# RCM-PBB_E1.net
KiCad netlist of a schematic drawn in EAGLE
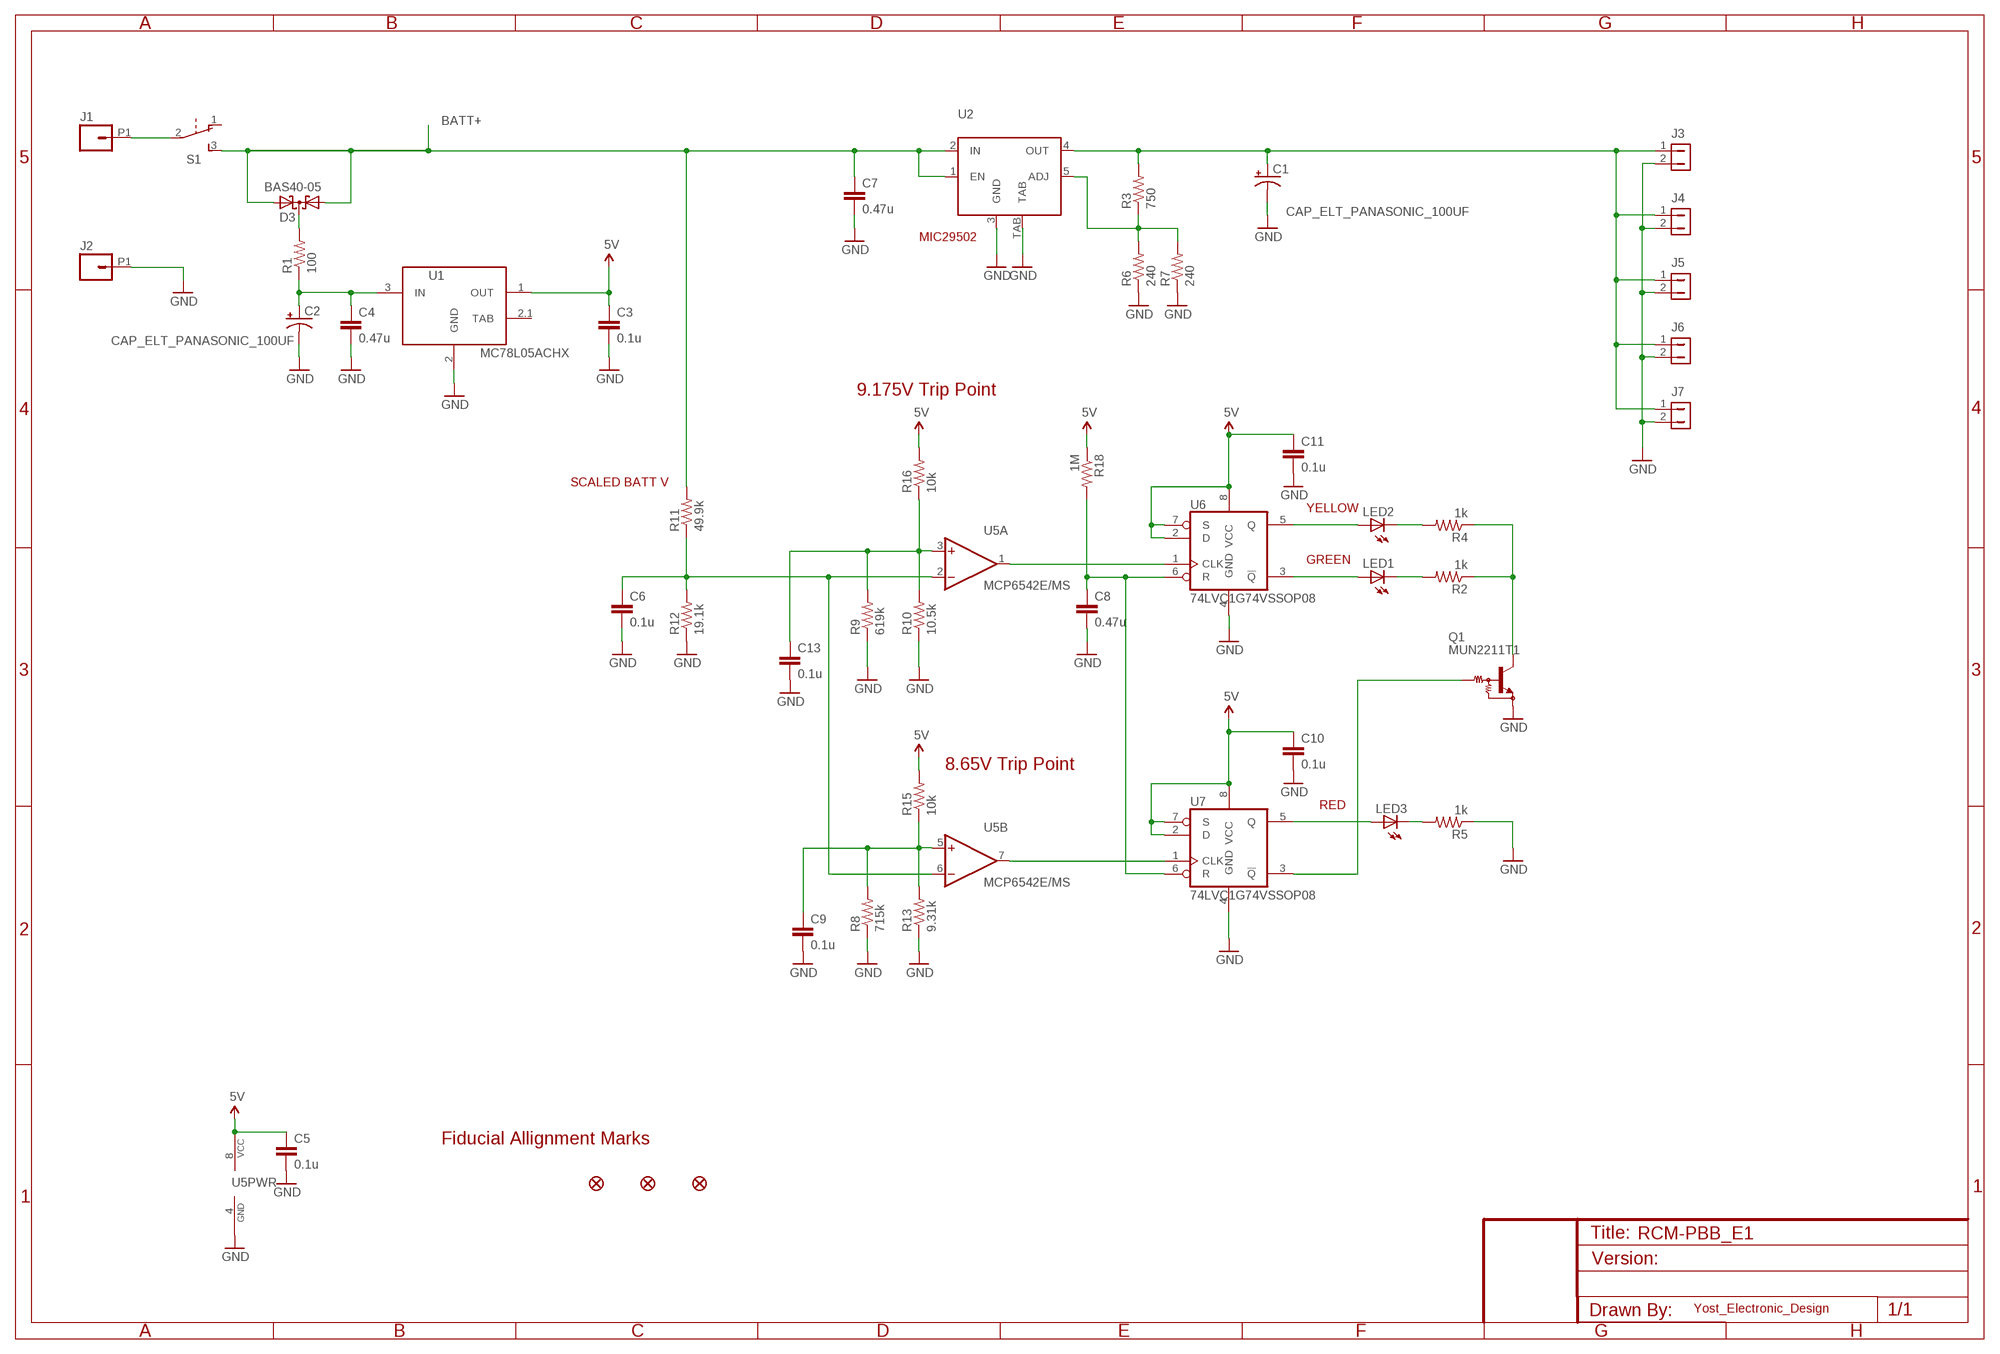
[diagram p0: schematic, sheet 1]

(export (version "E")
  (design (tool "Eeschema 10.0.6"))
  (components
    (comp (ref "C1")
      (value "CAP_ELT_PANASONIC_100UF")
      (footprint "eagle-import:PANASONIC-D8-ELT-CAP")
      (libsource (lib "eagle-import") (part "CAP_ELT_PANASONIC_100UF"))
    )
    (comp (ref "C2")
      (value "CAP_ELT_PANASONIC_100UF")
      (footprint "eagle-import:PANASONIC-D8-ELT-CAP")
      (libsource (lib "eagle-import") (part "CAP_ELT_PANASONIC_100UF"))
    )
    (comp (ref "C3")
      (value "0.1u")
      (footprint "eagle-import:0805")
      (libsource (lib "eagle-import") (part "CAP0805"))
    )
    (comp (ref "C4")
      (value "0.47u")
      (footprint "eagle-import:0805")
      (libsource (lib "eagle-import") (part "CAP0805"))
    )
    (comp (ref "C5")
      (value "0.1u")
      (footprint "eagle-import:0805")
      (libsource (lib "eagle-import") (part "CAP0805"))
    )
    (comp (ref "C6")
      (value "0.1u")
      (footprint "eagle-import:0805")
      (libsource (lib "eagle-import") (part "CAP0805"))
    )
    (comp (ref "C7")
      (value "0.47u")
      (footprint "eagle-import:0805")
      (libsource (lib "eagle-import") (part "CAP0805"))
    )
    (comp (ref "C8")
      (value "0.47u")
      (footprint "eagle-import:0805")
      (libsource (lib "eagle-import") (part "CAP0805"))
    )
    (comp (ref "C9")
      (value "0.1u")
      (footprint "eagle-import:0805")
      (libsource (lib "eagle-import") (part "CAP0805"))
    )
    (comp (ref "C10")
      (value "0.1u")
      (footprint "eagle-import:0805")
      (libsource (lib "eagle-import") (part "CAP0805"))
    )
    (comp (ref "C11")
      (value "0.1u")
      (footprint "eagle-import:0805")
      (libsource (lib "eagle-import") (part "CAP0805"))
    )
    (comp (ref "C13")
      (value "0.1u")
      (footprint "eagle-import:0805")
      (libsource (lib "eagle-import") (part "CAP0805"))
    )
    (comp (ref "D3")
      (value "BAS40-05")
      (footprint "eagle-import:SOT23")
      (libsource (lib "eagle-import") (part "BAS40-05"))
    )
    (comp (ref "J1")
      (value "ANDERSON_POWER_POLE")
      (footprint "eagle-import:ANDERSON_POWER_POLE")
      (libsource (lib "eagle-import") (part "ANDERSON_POWER_POLE"))
    )
    (comp (ref "J2")
      (value "ANDERSON_POWER_POLE")
      (footprint "eagle-import:ANDERSON_POWER_POLE")
      (libsource (lib "eagle-import") (part "ANDERSON_POWER_POLE"))
    )
    (comp (ref "J3")
      (value "CON1X2_SHROUDED")
      (footprint "eagle-import:HEADER_1X2_SHROUDED")
      (libsource (lib "eagle-import") (part "CON1X2_SHROUDED"))
    )
    (comp (ref "J4")
      (value "CON1X2_SHROUDED")
      (footprint "eagle-import:HEADER_1X2_SHROUDED")
      (libsource (lib "eagle-import") (part "CON1X2_SHROUDED"))
    )
    (comp (ref "J5")
      (value "CON1X2_SHROUDED")
      (footprint "eagle-import:HEADER_1X2_SHROUDED")
      (libsource (lib "eagle-import") (part "CON1X2_SHROUDED"))
    )
    (comp (ref "J6")
      (value "CON1X2_SHROUDED")
      (footprint "eagle-import:HEADER_1X2_SHROUDED")
      (libsource (lib "eagle-import") (part "CON1X2_SHROUDED"))
    )
    (comp (ref "J7")
      (value "CON1X2_SHROUDED")
      (footprint "eagle-import:HEADER_1X2_SHROUDED")
      (libsource (lib "eagle-import") (part "CON1X2_SHROUDED"))
    )
    (comp (ref "JP4")
      (value "FIDUCIAL1X2.5")
      (footprint "eagle-import:FIDUCIAL-1X2.5")
      (libsource (lib "eagle-import") (part "FIDUCIAL1X2.5"))
    )
    (comp (ref "JP5")
      (value "FIDUCIAL1X2.5")
      (footprint "eagle-import:FIDUCIAL-1X2.5")
      (libsource (lib "eagle-import") (part "FIDUCIAL1X2.5"))
    )
    (comp (ref "JP6")
      (value "FIDUCIAL1X2.5")
      (footprint "eagle-import:FIDUCIAL-1X2.5")
      (libsource (lib "eagle-import") (part "FIDUCIAL1X2.5"))
    )
    (comp (ref "LED1")
      (value "LEDCHIPLED_0805")
      (footprint "eagle-import:CHIPLED_0805")
      (libsource (lib "eagle-import") (part "LEDCHIPLED_0805"))
    )
    (comp (ref "LED2")
      (value "LEDCHIPLED_0805")
      (footprint "eagle-import:CHIPLED_0805")
      (libsource (lib "eagle-import") (part "LEDCHIPLED_0805"))
    )
    (comp (ref "LED3")
      (value "LEDCHIPLED_0805")
      (footprint "eagle-import:CHIPLED_0805")
      (libsource (lib "eagle-import") (part "LEDCHIPLED_0805"))
    )
    (comp (ref "Q1")
      (value "MUN2211T1")
      (footprint "eagle-import:SC59-BEC")
      (libsource (lib "eagle-import") (part "MUN2211T1"))
    )
    (comp (ref "R1")
      (value "100")
      (footprint "eagle-import:0805")
      (libsource (lib "eagle-import") (part "RESISTOR"))
    )
    (comp (ref "R2")
      (value "1k")
      (footprint "eagle-import:0805")
      (libsource (lib "eagle-import") (part "RESISTOR"))
    )
    (comp (ref "R3")
      (value "750")
      (footprint "eagle-import:0805")
      (libsource (lib "eagle-import") (part "RESISTOR"))
    )
    (comp (ref "R4")
      (value "1k")
      (footprint "eagle-import:0805")
      (libsource (lib "eagle-import") (part "RESISTOR"))
    )
    (comp (ref "R5")
      (value "1k")
      (footprint "eagle-import:0805")
      (libsource (lib "eagle-import") (part "RESISTOR"))
    )
    (comp (ref "R6")
      (value "240")
      (footprint "eagle-import:0805")
      (libsource (lib "eagle-import") (part "RESISTOR"))
    )
    (comp (ref "R7")
      (value "240")
      (footprint "eagle-import:0805")
      (libsource (lib "eagle-import") (part "RESISTOR"))
    )
    (comp (ref "R8")
      (value "715k")
      (footprint "eagle-import:0805")
      (libsource (lib "eagle-import") (part "RESISTOR"))
    )
    (comp (ref "R9")
      (value "619k")
      (footprint "eagle-import:0805")
      (libsource (lib "eagle-import") (part "RESISTOR"))
    )
    (comp (ref "R10")
      (value "10.5k")
      (footprint "eagle-import:0805")
      (libsource (lib "eagle-import") (part "RESISTOR"))
    )
    (comp (ref "R11")
      (value "49.9k")
      (footprint "eagle-import:0805")
      (libsource (lib "eagle-import") (part "RESISTOR"))
    )
    (comp (ref "R12")
      (value "19.1k")
      (footprint "eagle-import:0805")
      (libsource (lib "eagle-import") (part "RESISTOR"))
    )
    (comp (ref "R13")
      (value "9.31k")
      (footprint "eagle-import:0805")
      (libsource (lib "eagle-import") (part "RESISTOR"))
    )
    (comp (ref "R15")
      (value "10k")
      (footprint "eagle-import:0805")
      (libsource (lib "eagle-import") (part "RESISTOR"))
    )
    (comp (ref "R16")
      (value "10k")
      (footprint "eagle-import:0805")
      (libsource (lib "eagle-import") (part "RESISTOR"))
    )
    (comp (ref "R18")
      (value "1M")
      (footprint "eagle-import:0805")
      (libsource (lib "eagle-import") (part "RESISTOR"))
    )
    (comp (ref "S1")
      (value "SWITCH_SLIDE_ON_ON")
      (footprint "eagle-import:SWITCH_SLIDE_RA")
      (libsource (lib "eagle-import") (part "SWITCH_SLIDE_ON_ON"))
    )
    (comp (ref "U1")
      (value "MC78L05ACHX")
      (footprint "eagle-import:SOT89")
      (libsource (lib "eagle-import") (part "MC78L05ACHX"))
    )
    (comp (ref "U2")
      (value "MIC29502WU")
      (footprint "eagle-import:TO263-5")
      (libsource (lib "eagle-import") (part "MIC29502WU"))
    )
    (comp (ref "U5")
      (value "MCP6542E/MS")
      (footprint "eagle-import:MSOP8NOPAD")
      (libsource (lib "eagle-import") (part "MCP6542E/MS"))
    )
    (comp (ref "U6")
      (value "74LVC1G74VSSOP08")
      (footprint "eagle-import:VSSOP08")
      (libsource (lib "eagle-import") (part "74LVC1G74VSSOP08"))
    )
    (comp (ref "U7")
      (value "74LVC1G74VSSOP08")
      (footprint "eagle-import:VSSOP08")
      (libsource (lib "eagle-import") (part "74LVC1G74VSSOP08"))
    )
  )
  (nets
    (net (code "1") (name "/BATT+") (class "Default")
      (node (ref "C7") (pin "1") (pinfunction "1_1") (pintype "passive"))
      (node (ref "D3") (pin "1") (pinfunction "A1_1") (pintype "passive"))
      (node (ref "D3") (pin "2") (pinfunction "A2_2") (pintype "passive"))
      (node (ref "R11") (pin "2") (pinfunction "2_2") (pintype "passive"))
      (node (ref "S1") (pin "3") (pinfunction "S_3") (pintype "passive"))
      (node (ref "U2") (pin "1") (pinfunction "EN_1") (pintype "power_in"))
      (node (ref "U2") (pin "2") (pinfunction "IN_2") (pintype "input"))
    )
    (net (code "2") (name "5V") (class "Default")
      (node (ref "C10") (pin "1") (pinfunction "1_1") (pintype "passive"))
      (node (ref "C11") (pin "1") (pinfunction "1_1") (pintype "passive"))
      (node (ref "C3") (pin "1") (pinfunction "1_1") (pintype "passive"))
      (node (ref "C5") (pin "1") (pinfunction "1_1") (pintype "passive"))
      (node (ref "R15") (pin "2") (pinfunction "2_2") (pintype "passive"))
      (node (ref "R16") (pin "2") (pinfunction "2_2") (pintype "passive"))
      (node (ref "R18") (pin "1") (pinfunction "1_1") (pintype "passive"))
      (node (ref "U1") (pin "1") (pinfunction "OUT_1") (pintype "bidirectional"))
      (node (ref "U5") (pin "8") (pinfunction "VCC_8") (pintype "power_in"))
      (node (ref "U6") (pin "2") (pinfunction "D_2") (pintype "input"))
      (node (ref "U6") (pin "7") (pinfunction "S_7") (pintype "input"))
      (node (ref "U6") (pin "8") (pinfunction "VCC_8") (pintype "bidirectional"))
      (node (ref "U7") (pin "2") (pinfunction "D_2") (pintype "input"))
      (node (ref "U7") (pin "7") (pinfunction "S_7") (pintype "input"))
      (node (ref "U7") (pin "8") (pinfunction "VCC_8") (pintype "bidirectional"))
    )
    (net (code "3") (name "GND") (class "Default")
      (node (ref "C1") (pin "-") (pinfunction "-_-") (pintype "passive"))
      (node (ref "C10") (pin "2") (pinfunction "2_2") (pintype "passive"))
      (node (ref "C11") (pin "2") (pinfunction "2_2") (pintype "passive"))
      (node (ref "C13") (pin "2") (pinfunction "2_2") (pintype "passive"))
      (node (ref "C2") (pin "-") (pinfunction "-_-") (pintype "passive"))
      (node (ref "C3") (pin "2") (pinfunction "2_2") (pintype "passive"))
      (node (ref "C4") (pin "2") (pinfunction "2_2") (pintype "passive"))
      (node (ref "C5") (pin "2") (pinfunction "2_2") (pintype "passive"))
      (node (ref "C6") (pin "2") (pinfunction "2_2") (pintype "passive"))
      (node (ref "C7") (pin "2") (pinfunction "2_2") (pintype "passive"))
      (node (ref "C8") (pin "2") (pinfunction "2_2") (pintype "passive"))
      (node (ref "C9") (pin "2") (pinfunction "2_2") (pintype "passive"))
      (node (ref "J2") (pin "P1") (pinfunction "5_P1") (pintype "passive"))
      (node (ref "J3") (pin "2") (pinfunction "2_2") (pintype "passive"))
      (node (ref "J4") (pin "2") (pinfunction "2_2") (pintype "passive"))
      (node (ref "J5") (pin "2") (pinfunction "2_2") (pintype "passive"))
      (node (ref "J6") (pin "2") (pinfunction "2_2") (pintype "passive"))
      (node (ref "J7") (pin "2") (pinfunction "2_2") (pintype "passive"))
      (node (ref "Q1") (pin "E") (pinfunction "E_E") (pintype "passive"))
      (node (ref "R10") (pin "1") (pinfunction "1_1") (pintype "passive"))
      (node (ref "R12") (pin "1") (pinfunction "1_1") (pintype "passive"))
      (node (ref "R13") (pin "1") (pinfunction "1_1") (pintype "passive"))
      (node (ref "R5") (pin "1") (pinfunction "1_1") (pintype "passive"))
      (node (ref "R6") (pin "1") (pinfunction "1_1") (pintype "passive"))
      (node (ref "R7") (pin "1") (pinfunction "1_1") (pintype "passive"))
      (node (ref "R8") (pin "1") (pinfunction "1_1") (pintype "passive"))
      (node (ref "R9") (pin "1") (pinfunction "1_1") (pintype "passive"))
      (node (ref "U1") (pin "2") (pinfunction "GND_2") (pintype "bidirectional"))
      (node (ref "U2") (pin "3") (pinfunction "GND_3") (pintype "power_in"))
      (node (ref "U2") (pin "TAB") (pinfunction "TAB_TAB") (pintype "power_in"))
      (node (ref "U5") (pin "4") (pinfunction "GND_4") (pintype "power_in"))
      (node (ref "U6") (pin "4") (pinfunction "GND_4") (pintype "bidirectional"))
      (node (ref "U7") (pin "4") (pinfunction "GND_4") (pintype "bidirectional"))
    )
    (net (code "4") (name "Net-(D3-C)") (class "Default")
      (node (ref "D3") (pin "3") (pinfunction "C_3") (pintype "passive"))
      (node (ref "R1") (pin "2") (pinfunction "2_2") (pintype "passive"))
    )
    (net (code "5") (name "Net-(J1-5)") (class "Default")
      (node (ref "J1") (pin "P1") (pinfunction "5_P1") (pintype "passive"))
      (node (ref "S1") (pin "2") (pinfunction "P_2") (pintype "passive"))
    )
    (net (code "6") (name "Net-(LED1-PadC)") (class "Default")
      (node (ref "LED1") (pin "C") (pinfunction "C_C") (pintype "passive"))
      (node (ref "R2") (pin "2") (pinfunction "2_2") (pintype "passive"))
    )
    (net (code "7") (name "Net-(LED2-PadC)") (class "Default")
      (node (ref "LED2") (pin "C") (pinfunction "C_C") (pintype "passive"))
      (node (ref "R4") (pin "2") (pinfunction "2_2") (pintype "passive"))
    )
    (net (code "8") (name "Net-(LED3-PadC)") (class "Default")
      (node (ref "LED3") (pin "C") (pinfunction "C_C") (pintype "passive"))
      (node (ref "R5") (pin "2") (pinfunction "2_2") (pintype "passive"))
    )
    (net (code "9") (name "Net-(Q1-PadC)") (class "Default")
      (node (ref "Q1") (pin "C") (pinfunction "C_C") (pintype "passive"))
      (node (ref "R2") (pin "1") (pinfunction "1_1") (pintype "passive"))
      (node (ref "R4") (pin "1") (pinfunction "1_1") (pintype "passive"))
    )
    (net (code "10") (name "Net-(U1-IN)") (class "Default")
      (node (ref "C2") (pin "+") (pinfunction "+_+") (pintype "passive"))
      (node (ref "C4") (pin "1") (pinfunction "1_1") (pintype "passive"))
      (node (ref "R1") (pin "1") (pinfunction "1_1") (pintype "passive"))
      (node (ref "U1") (pin "3") (pinfunction "IN_3") (pintype "bidirectional"))
    )
    (net (code "11") (name "Net-(U2-ADJ)") (class "Default")
      (node (ref "R3") (pin "1") (pinfunction "1_1") (pintype "passive"))
      (node (ref "R6") (pin "2") (pinfunction "2_2") (pintype "passive"))
      (node (ref "R7") (pin "2") (pinfunction "2_2") (pintype "passive"))
      (node (ref "U2") (pin "5") (pinfunction "ADJ_5") (pintype "passive"))
    )
    (net (code "12") (name "Net-(U2-OUT)") (class "Default")
      (node (ref "C1") (pin "+") (pinfunction "+_+") (pintype "passive"))
      (node (ref "J3") (pin "1") (pinfunction "1_1") (pintype "passive"))
      (node (ref "J4") (pin "1") (pinfunction "1_1") (pintype "passive"))
      (node (ref "J5") (pin "1") (pinfunction "1_1") (pintype "passive"))
      (node (ref "J6") (pin "1") (pinfunction "1_1") (pintype "passive"))
      (node (ref "J7") (pin "1") (pinfunction "1_1") (pintype "passive"))
      (node (ref "R3") (pin "2") (pinfunction "2_2") (pintype "passive"))
      (node (ref "U2") (pin "4") (pinfunction "OUT_4") (pintype "input"))
    )
    (net (code "13") (name "Net-(U5A-+IN)") (class "Default")
      (node (ref "C13") (pin "1") (pinfunction "1_1") (pintype "passive"))
      (node (ref "R10") (pin "2") (pinfunction "2_2") (pintype "passive"))
      (node (ref "R16") (pin "1") (pinfunction "1_1") (pintype "passive"))
      (node (ref "R9") (pin "2") (pinfunction "2_2") (pintype "passive"))
      (node (ref "U5") (pin "3") (pinfunction "+IN_3") (pintype "input"))
    )
    (net (code "14") (name "Net-(U5A--IN)") (class "Default")
      (node (ref "C6") (pin "1") (pinfunction "1_1") (pintype "passive"))
      (node (ref "R11") (pin "1") (pinfunction "1_1") (pintype "passive"))
      (node (ref "R12") (pin "2") (pinfunction "2_2") (pintype "passive"))
      (node (ref "U5") (pin "2") (pinfunction "-IN_2") (pintype "input"))
      (node (ref "U5") (pin "6") (pinfunction "-IN_6") (pintype "input"))
    )
    (net (code "15") (name "Net-(U5A-OUT)") (class "Default")
      (node (ref "U5") (pin "1") (pinfunction "OUT_1") (pintype "output"))
      (node (ref "U6") (pin "1") (pinfunction "CLK_1") (pintype "input"))
    )
    (net (code "16") (name "Net-(U5B-+IN)") (class "Default")
      (node (ref "C9") (pin "1") (pinfunction "1_1") (pintype "passive"))
      (node (ref "R13") (pin "2") (pinfunction "2_2") (pintype "passive"))
      (node (ref "R15") (pin "1") (pinfunction "1_1") (pintype "passive"))
      (node (ref "R8") (pin "2") (pinfunction "2_2") (pintype "passive"))
      (node (ref "U5") (pin "5") (pinfunction "+IN_5") (pintype "input"))
    )
    (net (code "17") (name "Net-(U5B-OUT)") (class "Default")
      (node (ref "U5") (pin "7") (pinfunction "OUT_7") (pintype "output"))
      (node (ref "U7") (pin "1") (pinfunction "CLK_1") (pintype "input"))
    )
    (net (code "18") (name "Net-(U6-Q)") (class "Default")
      (node (ref "LED2") (pin "A") (pinfunction "A_A") (pintype "passive"))
      (node (ref "U6") (pin "5") (pinfunction "Q_5") (pintype "output"))
    )
    (net (code "19") (name "Net-(U6-R)") (class "Default")
      (node (ref "C8") (pin "1") (pinfunction "1_1") (pintype "passive"))
      (node (ref "R18") (pin "2") (pinfunction "2_2") (pintype "passive"))
      (node (ref "U6") (pin "6") (pinfunction "R_6") (pintype "input"))
      (node (ref "U7") (pin "6") (pinfunction "R_6") (pintype "input"))
    )
    (net (code "20") (name "Net-(U6-~{Q})") (class "Default")
      (node (ref "LED1") (pin "A") (pinfunction "A_A") (pintype "passive"))
      (node (ref "U6") (pin "3") (pinfunction "~{Q}_3") (pintype "output"))
    )
    (net (code "21") (name "Net-(U7-Q)") (class "Default")
      (node (ref "LED3") (pin "A") (pinfunction "A_A") (pintype "passive"))
      (node (ref "U7") (pin "5") (pinfunction "Q_5") (pintype "output"))
    )
    (net (code "22") (name "Net-(U7-~{Q})") (class "Default")
      (node (ref "Q1") (pin "B") (pinfunction "B_B") (pintype "passive"))
      (node (ref "U7") (pin "3") (pinfunction "~{Q}_3") (pintype "output"))
    )
    (net (code "23") (name "unconnected-(S1-O-Pad1)") (class "Default")
      (node (ref "S1") (pin "1") (pinfunction "O_1") (pintype "passive"))
    )
    (net (code "24") (name "unconnected-(U1-TAB-Pad2.1)") (class "Default")
      (node (ref "U1") (pin "2.1") (pinfunction "TAB_2.1") (pintype "bidirectional"))
    )
  )
)
